# OSO-MISC-20-008_Trinket_Adapter.net
KiCad netlist of a schematic drawn in EAGLE
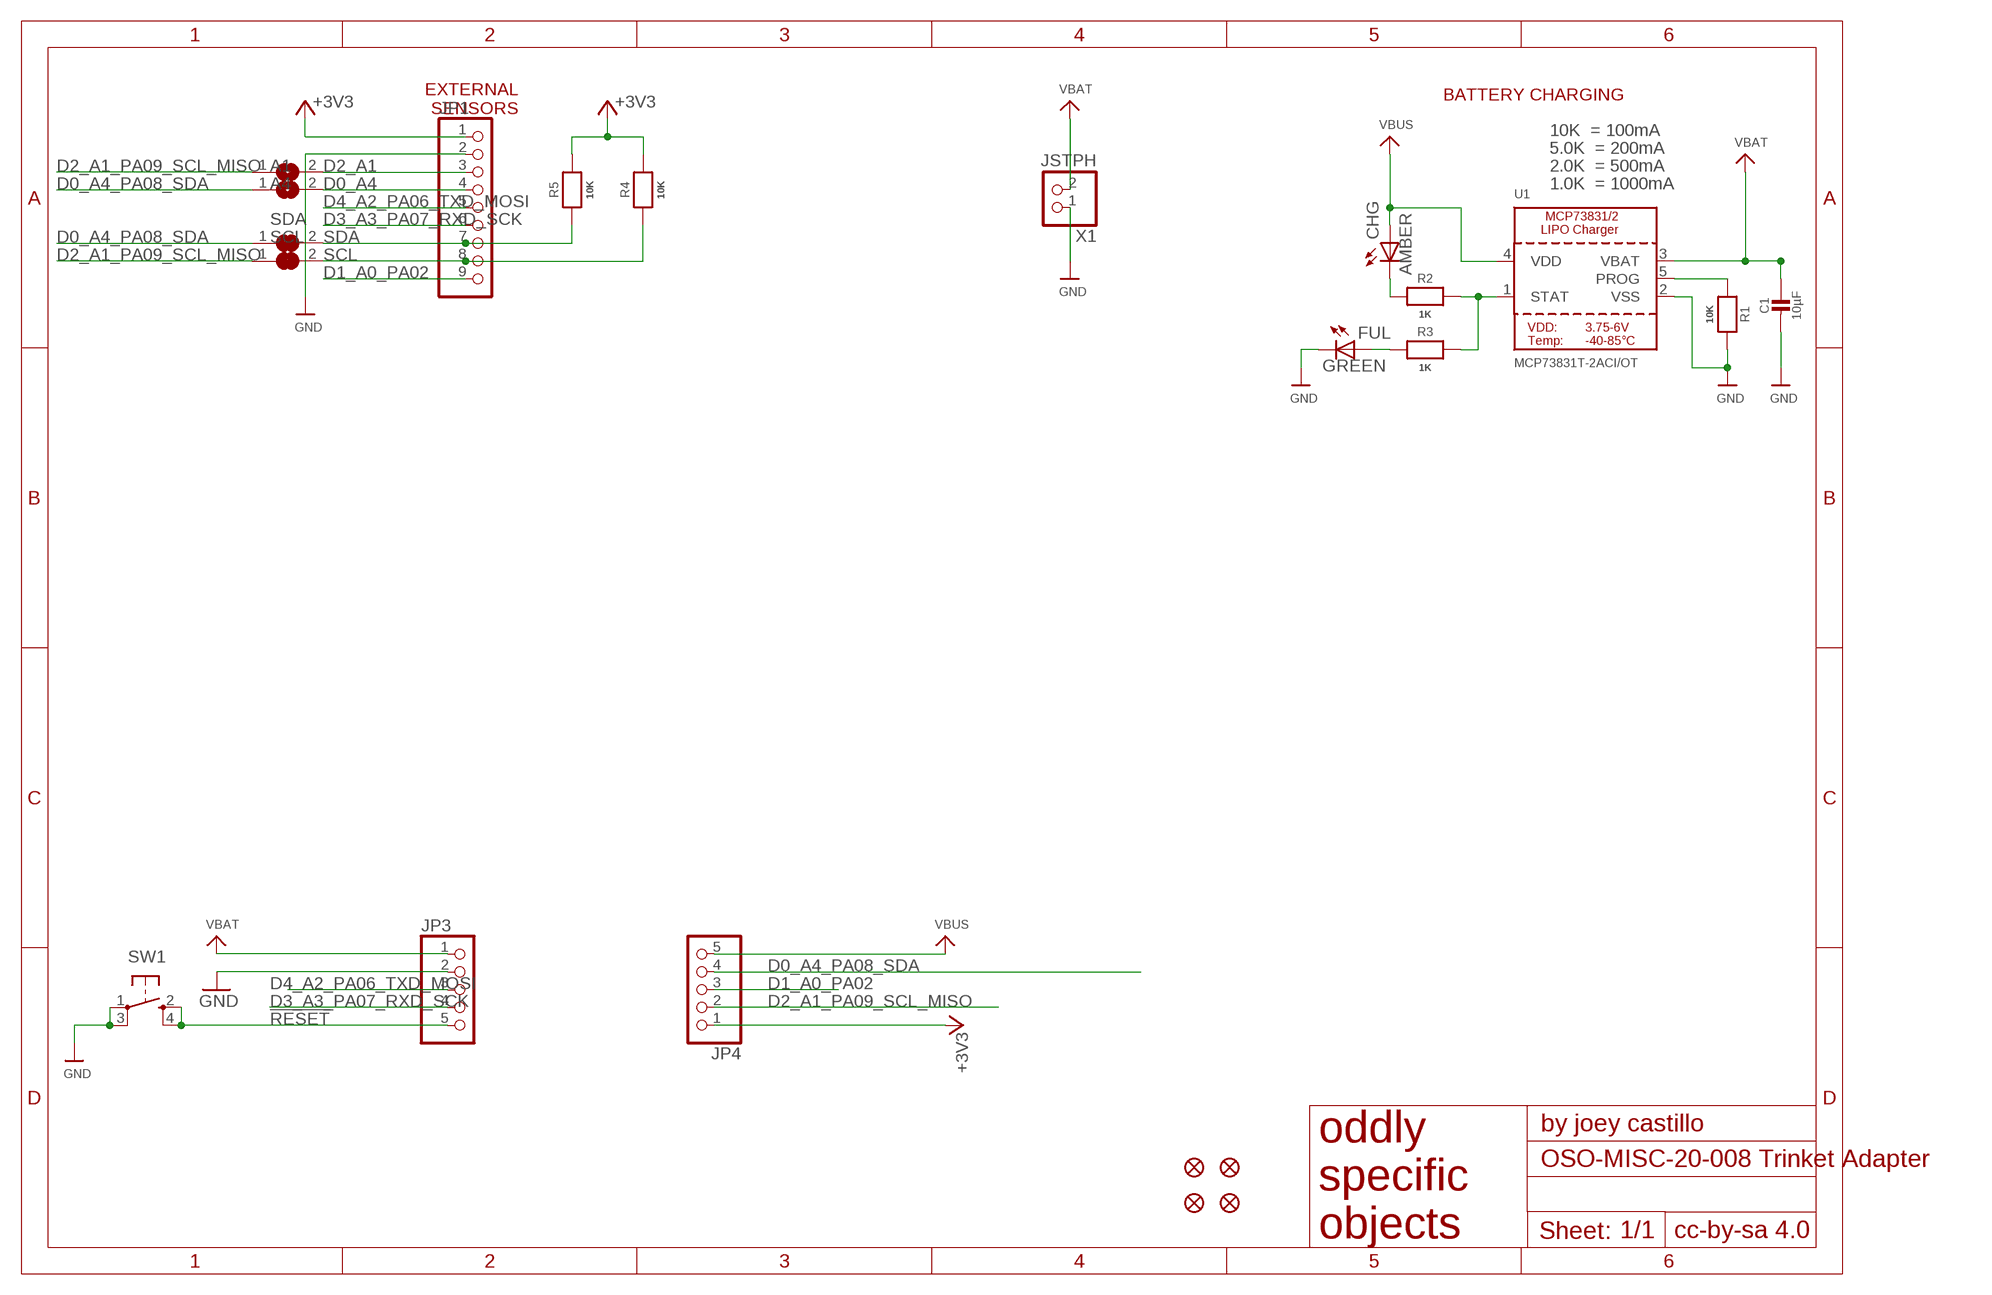
[diagram p0: schematic, sheet 1]

(export (version "E")
  (design (tool "Eeschema 10.0.6"))
  (components
    (comp (ref "A1")
      (value "SOLDERJUMPERREFLOW_NOPASTE")
      (footprint "eagle-import:SOLDERJUMPER_REFLOW_NOPASTE")
      (libsource (lib "eagle-import") (part "SOLDERJUMPERREFLOW_NOPASTE"))
    )
    (comp (ref "A4")
      (value "SOLDERJUMPERREFLOW_NOPASTE")
      (footprint "eagle-import:SOLDERJUMPER_REFLOW_NOPASTE")
      (libsource (lib "eagle-import") (part "SOLDERJUMPERREFLOW_NOPASTE"))
    )
    (comp (ref "C1")
      (value "10µF")
      (footprint "eagle-import:0805-NO")
      (libsource (lib "eagle-import") (part "CAP_CERAMIC0805-NOOUTLINE"))
    )
    (comp (ref "CHG")
      (value "AMBER")
      (footprint "eagle-import:CHIPLED_0805")
      (libsource (lib "eagle-import") (part "LEDCHIPLED_0805"))
    )
    (comp (ref "FID1")
      (value "FIDUCIAL_1MM")
      (footprint "eagle-import:FIDUCIAL_1MM")
      (libsource (lib "eagle-import") (part "FIDUCIAL_1MM"))
    )
    (comp (ref "FID2")
      (value "FIDUCIAL_1MM")
      (footprint "eagle-import:FIDUCIAL_1MM")
      (libsource (lib "eagle-import") (part "FIDUCIAL_1MM"))
    )
    (comp (ref "FID3")
      (value "FIDUCIAL_1MM")
      (footprint "eagle-import:FIDUCIAL_1MM")
      (libsource (lib "eagle-import") (part "FIDUCIAL_1MM"))
    )
    (comp (ref "FID4")
      (value "FIDUCIAL_1MM")
      (footprint "eagle-import:FIDUCIAL_1MM")
      (libsource (lib "eagle-import") (part "FIDUCIAL_1MM"))
    )
    (comp (ref "FUL")
      (value "GREEN")
      (footprint "eagle-import:CHIPLED_0805")
      (libsource (lib "eagle-import") (part "LEDCHIPLED_0805"))
    )
    (comp (ref "JP1")
      (value "HEADER-1X9_JSTSH")
      (footprint "eagle-import:JST_SH9")
      (libsource (lib "eagle-import") (part "HEADER-1X9_JSTSH"))
    )
    (comp (ref "JP3")
      (value "HEADER-1X576MIL")
      (footprint "eagle-import:1X05_ROUND_76")
      (libsource (lib "eagle-import") (part "HEADER-1X576MIL"))
    )
    (comp (ref "JP4")
      (value "HEADER-1X576MIL")
      (footprint "eagle-import:1X05_ROUND_76")
      (libsource (lib "eagle-import") (part "HEADER-1X576MIL"))
    )
    (comp (ref "R1")
      (value "10K")
      (footprint "eagle-import:0805-NO")
      (libsource (lib "eagle-import") (part "RESISTOR0805_NOOUTLINE"))
    )
    (comp (ref "R2")
      (value "1K")
      (footprint "eagle-import:0805-NO")
      (libsource (lib "eagle-import") (part "RESISTOR0805_NOOUTLINE"))
    )
    (comp (ref "R3")
      (value "1K")
      (footprint "eagle-import:0805-NO")
      (libsource (lib "eagle-import") (part "RESISTOR0805_NOOUTLINE"))
    )
    (comp (ref "R4")
      (value "10K")
      (footprint "eagle-import:0805-NO")
      (libsource (lib "eagle-import") (part "RESISTOR0805_NOOUTLINE"))
    )
    (comp (ref "R5")
      (value "10K")
      (footprint "eagle-import:0805-NO")
      (libsource (lib "eagle-import") (part "RESISTOR0805_NOOUTLINE"))
    )
    (comp (ref "SCL")
      (value "MICROBUILDER_SOLDERJUMPER_CLOSED")
      (footprint "eagle-import:MICROBUILDER_SOLDERJUMPER_CLOSEDWIRE")
      (libsource (lib "eagle-import") (part "MICROBUILDER_SOLDERJUMPER_CLOSED"))
    )
    (comp (ref "SDA")
      (value "MICROBUILDER_SOLDERJUMPER_CLOSED")
      (footprint "eagle-import:MICROBUILDER_SOLDERJUMPER_CLOSEDWIRE")
      (libsource (lib "eagle-import") (part "MICROBUILDER_SOLDERJUMPER_CLOSED"))
    )
    (comp (ref "SW1")
      (value "SPST_TACT-KMR2")
      (footprint "eagle-import:KMR2")
      (libsource (lib "eagle-import") (part "SPST_TACT-KMR2"))
    )
    (comp (ref "U1")
      (value "MCP73831T-2ACI/OT")
      (footprint "eagle-import:SOT23-5")
      (libsource (lib "eagle-import") (part "MCP73831/2"))
    )
    (comp (ref "X1")
      (value "JSTPH")
      (footprint "eagle-import:JSTPH2")
      (libsource (lib "eagle-import") (part "CON_JST_PH_2PIN"))
    )
  )
  (nets
    (net (code "1") (name "+3V3") (class "Default")
      (node (ref "JP1") (pin "1") (pinfunction "1_1") (pintype "passive"))
      (node (ref "JP4") (pin "1") (pinfunction "1_1") (pintype "passive"))
      (node (ref "R4") (pin "2") (pinfunction "2_2") (pintype "passive"))
      (node (ref "R5") (pin "2") (pinfunction "2_2") (pintype "passive"))
    )
    (net (code "2") (name "/D0_A4") (class "Default")
      (node (ref "A4") (pin "2") (pinfunction "2_2") (pintype "passive"))
      (node (ref "JP1") (pin "4") (pinfunction "4_4") (pintype "passive"))
    )
    (net (code "3") (name "/D0_A4_PA08_SDA") (class "Default")
      (node (ref "A4") (pin "1") (pinfunction "1_1") (pintype "passive"))
      (node (ref "JP4") (pin "4") (pinfunction "4_4") (pintype "passive"))
      (node (ref "SDA") (pin "1") (pinfunction "1_1") (pintype "passive"))
    )
    (net (code "4") (name "/D1_A0_PA02") (class "Default")
      (node (ref "JP1") (pin "9") (pinfunction "9_9") (pintype "passive"))
      (node (ref "JP4") (pin "3") (pinfunction "3_3") (pintype "passive"))
    )
    (net (code "5") (name "/D2_A1") (class "Default")
      (node (ref "A1") (pin "2") (pinfunction "2_2") (pintype "passive"))
      (node (ref "JP1") (pin "3") (pinfunction "3_3") (pintype "passive"))
    )
    (net (code "6") (name "/D2_A1_PA09_SCL_MISO") (class "Default")
      (node (ref "A1") (pin "1") (pinfunction "1_1") (pintype "passive"))
      (node (ref "JP4") (pin "2") (pinfunction "2_2") (pintype "passive"))
      (node (ref "SCL") (pin "1") (pinfunction "1_1") (pintype "passive"))
    )
    (net (code "7") (name "/D3_A3_PA07_RXD_SCK") (class "Default")
      (node (ref "JP1") (pin "6") (pinfunction "6_6") (pintype "passive"))
      (node (ref "JP3") (pin "4") (pinfunction "4_4") (pintype "passive"))
    )
    (net (code "8") (name "/D4_A2_PA06_TXD_MOSI") (class "Default")
      (node (ref "JP1") (pin "5") (pinfunction "5_5") (pintype "passive"))
      (node (ref "JP3") (pin "3") (pinfunction "3_3") (pintype "passive"))
    )
    (net (code "9") (name "/SCL") (class "Default")
      (node (ref "JP1") (pin "8") (pinfunction "8_8") (pintype "passive"))
      (node (ref "R4") (pin "1") (pinfunction "1_1") (pintype "passive"))
      (node (ref "SCL") (pin "2") (pinfunction "2_2") (pintype "passive"))
    )
    (net (code "10") (name "/SDA") (class "Default")
      (node (ref "JP1") (pin "7") (pinfunction "7_7") (pintype "passive"))
      (node (ref "R5") (pin "1") (pinfunction "1_1") (pintype "passive"))
      (node (ref "SDA") (pin "2") (pinfunction "2_2") (pintype "passive"))
    )
    (net (code "11") (name "/~{RESET}") (class "Default")
      (node (ref "JP3") (pin "5") (pinfunction "5_5") (pintype "passive"))
      (node (ref "SW1") (pin "2") (pinfunction "S_2") (pintype "passive"))
      (node (ref "SW1") (pin "4") (pinfunction "S1_4") (pintype "passive"))
    )
    (net (code "12") (name "GND") (class "Default")
      (node (ref "C1") (pin "2") (pinfunction "2_2") (pintype "passive"))
      (node (ref "FUL") (pin "C") (pinfunction "C_C") (pintype "passive"))
      (node (ref "JP1") (pin "2") (pinfunction "2_2") (pintype "passive"))
      (node (ref "JP3") (pin "2") (pinfunction "2_2") (pintype "passive"))
      (node (ref "R1") (pin "2") (pinfunction "2_2") (pintype "passive"))
      (node (ref "SW1") (pin "1") (pinfunction "P_1") (pintype "passive"))
      (node (ref "SW1") (pin "3") (pinfunction "P1_3") (pintype "passive"))
      (node (ref "U1") (pin "2") (pinfunction "VSS_2") (pintype "power_in"))
      (node (ref "X1") (pin "1") (pinfunction "1_1") (pintype "passive"))
    )
    (net (code "13") (name "Net-(CHG-PadC)") (class "Default")
      (node (ref "CHG") (pin "C") (pinfunction "C_C") (pintype "passive"))
      (node (ref "R2") (pin "1") (pinfunction "1_1") (pintype "passive"))
    )
    (net (code "14") (name "Net-(FUL-PadA)") (class "Default")
      (node (ref "FUL") (pin "A") (pinfunction "A_A") (pintype "passive"))
      (node (ref "R3") (pin "1") (pinfunction "1_1") (pintype "passive"))
    )
    (net (code "15") (name "Net-(U1-PROG)") (class "Default")
      (node (ref "R1") (pin "1") (pinfunction "1_1") (pintype "passive"))
      (node (ref "U1") (pin "5") (pinfunction "PROG_5") (pintype "input"))
    )
    (net (code "16") (name "Net-(U1-STAT)") (class "Default")
      (node (ref "R2") (pin "2") (pinfunction "2_2") (pintype "passive"))
      (node (ref "R3") (pin "2") (pinfunction "2_2") (pintype "passive"))
      (node (ref "U1") (pin "1") (pinfunction "STAT_1") (pintype "output"))
    )
    (net (code "17") (name "VBAT") (class "Default")
      (node (ref "C1") (pin "1") (pinfunction "1_1") (pintype "passive"))
      (node (ref "JP3") (pin "1") (pinfunction "1_1") (pintype "passive"))
      (node (ref "U1") (pin "3") (pinfunction "VBAT_3") (pintype "power_in"))
      (node (ref "X1") (pin "2") (pinfunction "2_2") (pintype "passive"))
    )
    (net (code "18") (name "VBUS") (class "Default")
      (node (ref "CHG") (pin "A") (pinfunction "A_A") (pintype "passive"))
      (node (ref "JP4") (pin "5") (pinfunction "5_5") (pintype "passive"))
      (node (ref "U1") (pin "4") (pinfunction "VDD_4") (pintype "power_in"))
    )
  )
)
